# RTDS.net
KiCad netlist of a schematic drawn in EAGLE
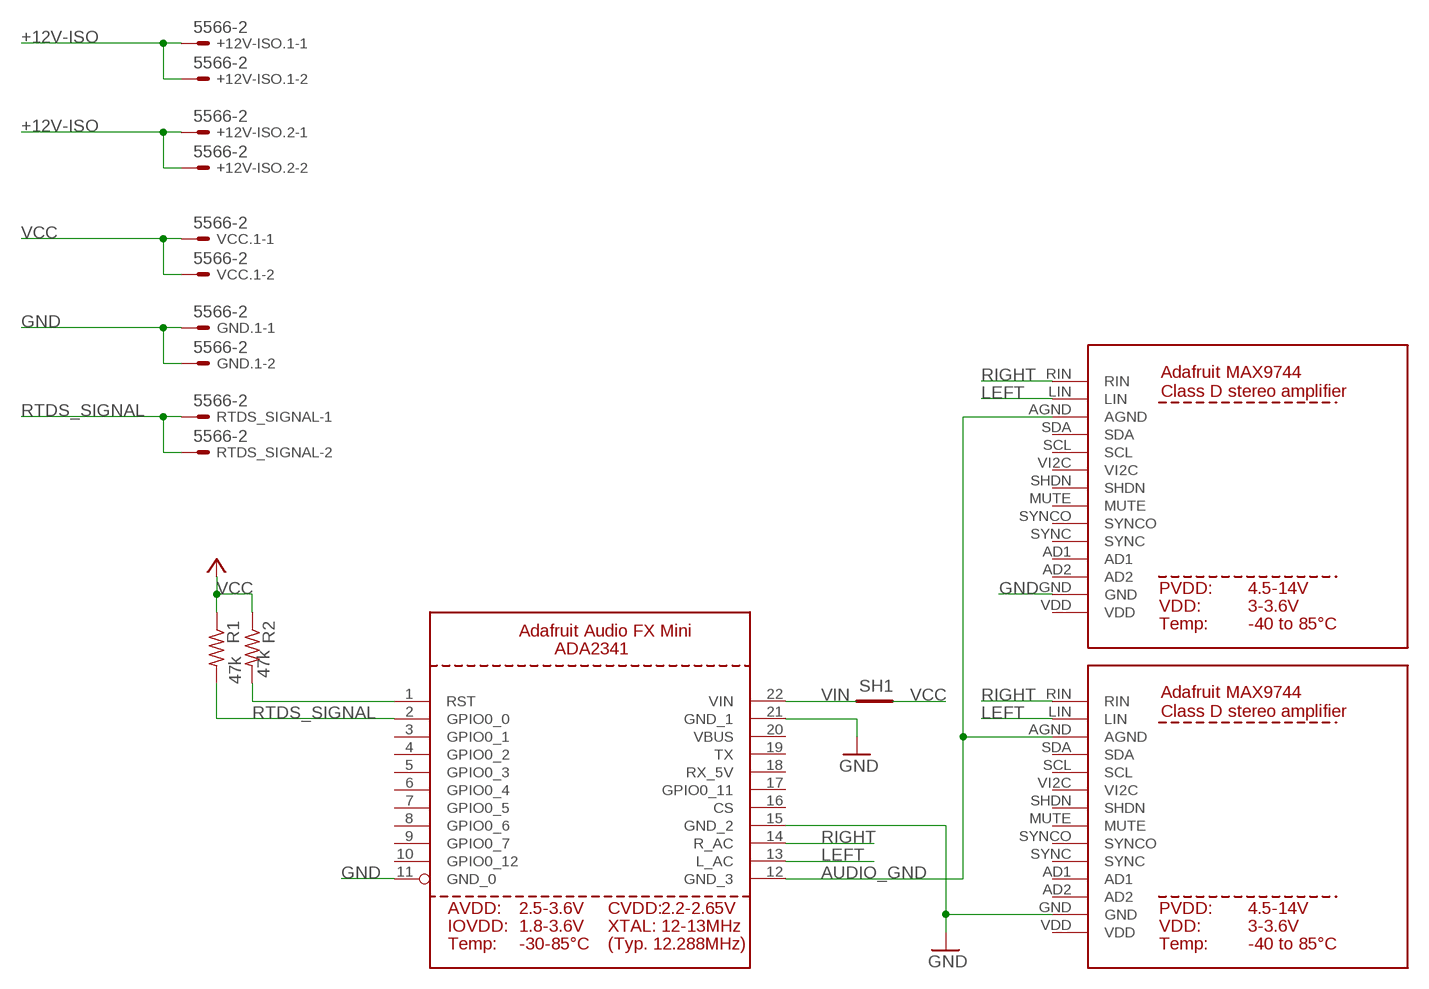
[diagram p0: schematic, sheet 1]

(export (version "E")
  (design (tool "Eeschema 10.0.6"))
  (components
    (comp (ref "+12V-ISO.1")
      (value "5566-2")
      (footprint "eagle-import:5566-2")
      (fields (field (name "MF") "MOLEX"))
      (libsource (lib "eagle-import") (part "5566-2"))
    )
    (comp (ref "+12V-ISO.2")
      (value "5566-2")
      (footprint "eagle-import:5566-2")
      (fields (field (name "MF") "MOLEX"))
      (libsource (lib "eagle-import") (part "5566-2"))
    )
    (comp (ref "GND.1")
      (value "5566-2")
      (footprint "eagle-import:5566-2")
      (fields (field (name "MF") "MOLEX"))
      (libsource (lib "eagle-import") (part "5566-2"))
    )
    (comp (ref "R1")
      (value "47k")
      (footprint "eagle-import:R0805")
      (libsource (lib "eagle-import") (part "R-US_R0805"))
    )
    (comp (ref "R2")
      (value "47k")
      (footprint "eagle-import:R0805")
      (libsource (lib "eagle-import") (part "R-US_R0805"))
    )
    (comp (ref "RTDS_SIGNAL")
      (value "5566-2")
      (footprint "eagle-import:5566-2")
      (fields (field (name "MF") "MOLEX"))
      (libsource (lib "eagle-import") (part "5566-2"))
    )
    (comp (ref "SH1")
      (value "SHORTT5")
      (footprint "eagle-import:SHORT_TOP-50")
      (libsource (lib "eagle-import") (part "SHORTT5"))
    )
    (comp (ref "U$1")
      (value "MAX9744")
      (footprint "eagle-import:MAX9744")
      (libsource (lib "eagle-import") (part "MAX9744"))
    )
    (comp (ref "U$2")
      (value "ADA-SOUNDFX")
      (footprint "eagle-import:ADA-SOUNDFX")
      (libsource (lib "eagle-import") (part "ADA-SOUNDFX"))
    )
    (comp (ref "U$3")
      (value "MAX9744")
      (footprint "eagle-import:MAX9744")
      (libsource (lib "eagle-import") (part "MAX9744"))
    )
    (comp (ref "VCC.1")
      (value "5566-2")
      (footprint "eagle-import:5566-2")
      (fields (field (name "MF") "MOLEX"))
      (libsource (lib "eagle-import") (part "5566-2"))
    )
  )
  (nets
    (net (code "1") (name "/+12V-ISO") (class "Default")
      (node (ref "+12V-ISO.1") (pin "1") (pinfunction "S_1") (pintype "passive"))
      (node (ref "+12V-ISO.1") (pin "2") (pinfunction "S_2") (pintype "passive"))
      (node (ref "+12V-ISO.2") (pin "1") (pinfunction "S_1") (pintype "passive"))
      (node (ref "+12V-ISO.2") (pin "2") (pinfunction "S_2") (pintype "passive"))
    )
    (net (code "2") (name "/AUDIO_GND") (class "Default")
      (node (ref "U$1") (pin "AGND") (pinfunction "AGND_AGND") (pintype "bidirectional"))
      (node (ref "U$2") (pin "12") (pinfunction "GND_3_12") (pintype "power_in"))
      (node (ref "U$3") (pin "AGND") (pinfunction "AGND_AGND") (pintype "bidirectional"))
    )
    (net (code "3") (name "/LEFT") (class "Default")
      (node (ref "U$1") (pin "LIN") (pinfunction "LIN_LIN") (pintype "bidirectional"))
      (node (ref "U$2") (pin "13") (pinfunction "L_AC_13") (pintype "bidirectional"))
      (node (ref "U$3") (pin "LIN") (pinfunction "LIN_LIN") (pintype "bidirectional"))
    )
    (net (code "4") (name "/RIGHT") (class "Default")
      (node (ref "U$1") (pin "RIN") (pinfunction "RIN_RIN") (pintype "bidirectional"))
      (node (ref "U$2") (pin "14") (pinfunction "R_AC_14") (pintype "bidirectional"))
      (node (ref "U$3") (pin "RIN") (pinfunction "RIN_RIN") (pintype "bidirectional"))
    )
    (net (code "5") (name "/RTDS_SIGNAL") (class "Default")
      (node (ref "R1") (pin "2") (pinfunction "2_2") (pintype "passive"))
      (node (ref "RTDS_SIGNAL") (pin "1") (pinfunction "S_1") (pintype "passive"))
      (node (ref "RTDS_SIGNAL") (pin "2") (pinfunction "S_2") (pintype "passive"))
      (node (ref "U$2") (pin "2") (pinfunction "GPIO0_0_2") (pintype "bidirectional"))
    )
    (net (code "6") (name "/VIN") (class "Default")
      (node (ref "SH1") (pin "1") (pinfunction "P$1_1") (pintype "bidirectional"))
      (node (ref "U$2") (pin "22") (pinfunction "VIN_22") (pintype "power_in"))
    )
    (net (code "7") (name "GND") (class "Default")
      (node (ref "GND.1") (pin "1") (pinfunction "S_1") (pintype "passive"))
      (node (ref "GND.1") (pin "2") (pinfunction "S_2") (pintype "passive"))
      (node (ref "U$1") (pin "GND") (pinfunction "GND_GND") (pintype "bidirectional"))
      (node (ref "U$2") (pin "11") (pinfunction "GND_0_11") (pintype "power_in"))
      (node (ref "U$2") (pin "15") (pinfunction "GND_2_15") (pintype "bidirectional"))
      (node (ref "U$2") (pin "21") (pinfunction "GND_1_21") (pintype "power_in"))
      (node (ref "U$3") (pin "GND") (pinfunction "GND_GND") (pintype "bidirectional"))
    )
    (net (code "8") (name "Net-(U$2-RST)") (class "Default")
      (node (ref "R2") (pin "2") (pinfunction "2_2") (pintype "passive"))
      (node (ref "U$2") (pin "1") (pinfunction "RST_1") (pintype "bidirectional"))
    )
    (net (code "9") (name "VCC") (class "Default")
      (node (ref "R1") (pin "1") (pinfunction "1_1") (pintype "passive"))
      (node (ref "R2") (pin "1") (pinfunction "1_1") (pintype "passive"))
      (node (ref "SH1") (pin "2") (pinfunction "P$2_2") (pintype "bidirectional"))
      (node (ref "VCC.1") (pin "1") (pinfunction "S_1") (pintype "passive"))
      (node (ref "VCC.1") (pin "2") (pinfunction "S_2") (pintype "passive"))
    )
    (net (code "10") (name "unconnected-(U$1-PadAD1)") (class "Default")
      (node (ref "U$1") (pin "AD1") (pinfunction "AD1_AD1") (pintype "bidirectional"))
    )
    (net (code "11") (name "unconnected-(U$1-PadAD2)") (class "Default")
      (node (ref "U$1") (pin "AD2") (pinfunction "AD2_AD2") (pintype "bidirectional"))
    )
    (net (code "12") (name "unconnected-(U$1-PadMUTE)") (class "Default")
      (node (ref "U$1") (pin "MUTE") (pinfunction "MUTE_MUTE") (pintype "bidirectional"))
    )
    (net (code "13") (name "unconnected-(U$1-PadSCL)") (class "Default")
      (node (ref "U$1") (pin "SCL") (pinfunction "SCL_SCL") (pintype "bidirectional"))
    )
    (net (code "14") (name "unconnected-(U$1-PadSDA)") (class "Default")
      (node (ref "U$1") (pin "SDA") (pinfunction "SDA_SDA") (pintype "bidirectional"))
    )
    (net (code "15") (name "unconnected-(U$1-PadSHDN)") (class "Default")
      (node (ref "U$1") (pin "SHDN") (pinfunction "SHDN_SHDN") (pintype "bidirectional"))
    )
    (net (code "16") (name "unconnected-(U$1-PadSYNC)") (class "Default")
      (node (ref "U$1") (pin "SYNC") (pinfunction "SYNC_SYNC") (pintype "bidirectional"))
    )
    (net (code "17") (name "unconnected-(U$1-PadSYNCO)") (class "Default")
      (node (ref "U$1") (pin "SYNCO") (pinfunction "SYNCO_SYNCO") (pintype "bidirectional"))
    )
    (net (code "18") (name "unconnected-(U$1-PadVDD)") (class "Default")
      (node (ref "U$1") (pin "VDD") (pinfunction "VDD_VDD") (pintype "bidirectional"))
    )
    (net (code "19") (name "unconnected-(U$1-PadVI2C)") (class "Default")
      (node (ref "U$1") (pin "VI2C") (pinfunction "VI2C_VI2C") (pintype "bidirectional"))
    )
    (net (code "20") (name "unconnected-(U$2-CS-Pad16)") (class "Default")
      (node (ref "U$2") (pin "16") (pinfunction "CS_16") (pintype "bidirectional"))
    )
    (net (code "21") (name "unconnected-(U$2-GPIO0_1-Pad3)") (class "Default")
      (node (ref "U$2") (pin "3") (pinfunction "GPIO0_1_3") (pintype "bidirectional"))
    )
    (net (code "22") (name "unconnected-(U$2-GPIO0_2-Pad4)") (class "Default")
      (node (ref "U$2") (pin "4") (pinfunction "GPIO0_2_4") (pintype "bidirectional"))
    )
    (net (code "23") (name "unconnected-(U$2-GPIO0_3-Pad5)") (class "Default")
      (node (ref "U$2") (pin "5") (pinfunction "GPIO0_3_5") (pintype "bidirectional"))
    )
    (net (code "24") (name "unconnected-(U$2-GPIO0_4-Pad6)") (class "Default")
      (node (ref "U$2") (pin "6") (pinfunction "GPIO0_4_6") (pintype "bidirectional"))
    )
    (net (code "25") (name "unconnected-(U$2-GPIO0_5-Pad7)") (class "Default")
      (node (ref "U$2") (pin "7") (pinfunction "GPIO0_5_7") (pintype "bidirectional"))
    )
    (net (code "26") (name "unconnected-(U$2-GPIO0_6-Pad8)") (class "Default")
      (node (ref "U$2") (pin "8") (pinfunction "GPIO0_6_8") (pintype "bidirectional"))
    )
    (net (code "27") (name "unconnected-(U$2-GPIO0_7-Pad9)") (class "Default")
      (node (ref "U$2") (pin "9") (pinfunction "GPIO0_7_9") (pintype "bidirectional"))
    )
    (net (code "28") (name "unconnected-(U$2-GPIO0_11-Pad17)") (class "Default")
      (node (ref "U$2") (pin "17") (pinfunction "GPIO0_11_17") (pintype "bidirectional"))
    )
    (net (code "29") (name "unconnected-(U$2-GPIO0_12-Pad10)") (class "Default")
      (node (ref "U$2") (pin "10") (pinfunction "GPIO0_12_10") (pintype "bidirectional"))
    )
    (net (code "30") (name "unconnected-(U$2-RX_5V-Pad18)") (class "Default")
      (node (ref "U$2") (pin "18") (pinfunction "RX_5V_18") (pintype "bidirectional"))
    )
    (net (code "31") (name "unconnected-(U$2-TX-Pad19)") (class "Default")
      (node (ref "U$2") (pin "19") (pinfunction "TX_19") (pintype "bidirectional"))
    )
    (net (code "32") (name "unconnected-(U$2-VBUS-Pad20)") (class "Default")
      (node (ref "U$2") (pin "20") (pinfunction "VBUS_20") (pintype "bidirectional"))
    )
    (net (code "33") (name "unconnected-(U$3-PadAD1)") (class "Default")
      (node (ref "U$3") (pin "AD1") (pinfunction "AD1_AD1") (pintype "bidirectional"))
    )
    (net (code "34") (name "unconnected-(U$3-PadAD2)") (class "Default")
      (node (ref "U$3") (pin "AD2") (pinfunction "AD2_AD2") (pintype "bidirectional"))
    )
    (net (code "35") (name "unconnected-(U$3-PadMUTE)") (class "Default")
      (node (ref "U$3") (pin "MUTE") (pinfunction "MUTE_MUTE") (pintype "bidirectional"))
    )
    (net (code "36") (name "unconnected-(U$3-PadSCL)") (class "Default")
      (node (ref "U$3") (pin "SCL") (pinfunction "SCL_SCL") (pintype "bidirectional"))
    )
    (net (code "37") (name "unconnected-(U$3-PadSDA)") (class "Default")
      (node (ref "U$3") (pin "SDA") (pinfunction "SDA_SDA") (pintype "bidirectional"))
    )
    (net (code "38") (name "unconnected-(U$3-PadSHDN)") (class "Default")
      (node (ref "U$3") (pin "SHDN") (pinfunction "SHDN_SHDN") (pintype "bidirectional"))
    )
    (net (code "39") (name "unconnected-(U$3-PadSYNC)") (class "Default")
      (node (ref "U$3") (pin "SYNC") (pinfunction "SYNC_SYNC") (pintype "bidirectional"))
    )
    (net (code "40") (name "unconnected-(U$3-PadSYNCO)") (class "Default")
      (node (ref "U$3") (pin "SYNCO") (pinfunction "SYNCO_SYNCO") (pintype "bidirectional"))
    )
    (net (code "41") (name "unconnected-(U$3-PadVDD)") (class "Default")
      (node (ref "U$3") (pin "VDD") (pinfunction "VDD_VDD") (pintype "bidirectional"))
    )
    (net (code "42") (name "unconnected-(U$3-PadVI2C)") (class "Default")
      (node (ref "U$3") (pin "VI2C") (pinfunction "VI2C_VI2C") (pintype "bidirectional"))
    )
  )
)
